# Patch.net
KiCad netlist of a schematic drawn in EAGLE
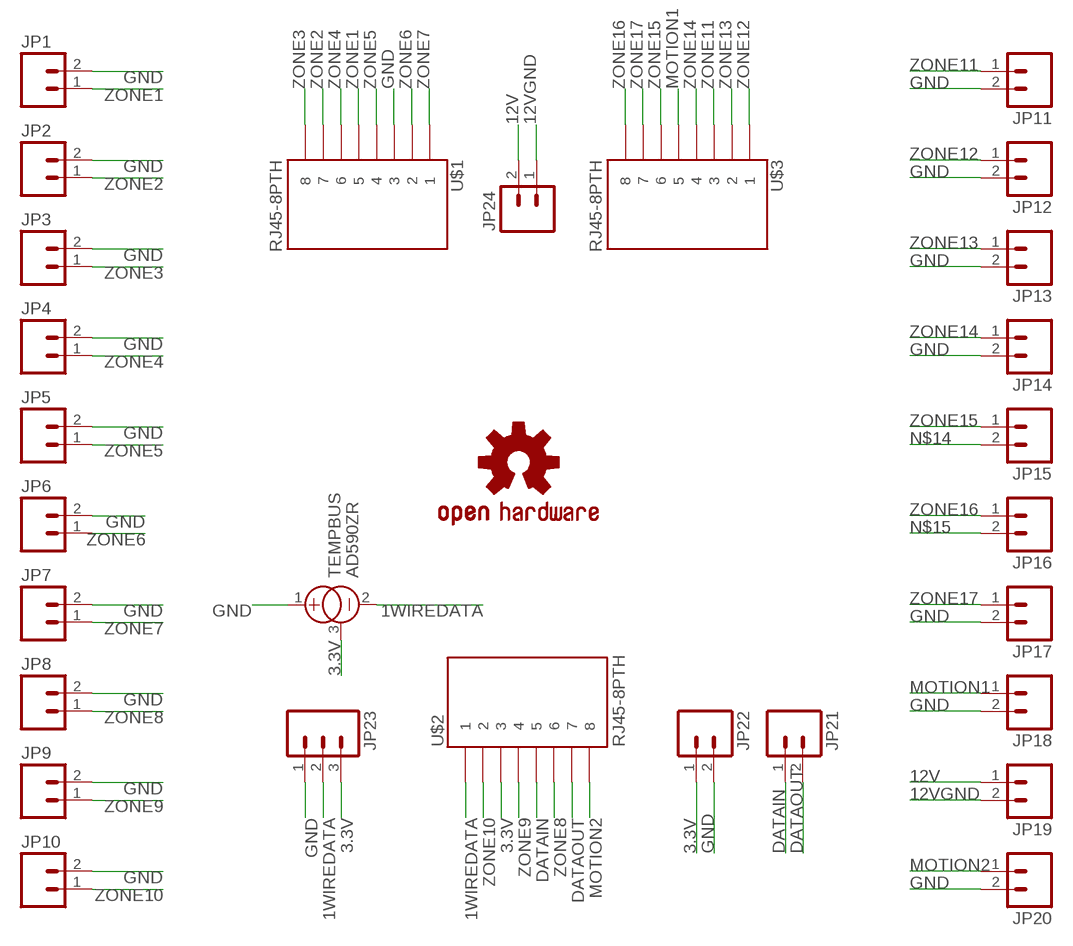
[diagram p0: schematic, sheet 1]

(export (version "E")
  (design (tool "Eeschema 10.0.6"))
  (components
    (comp (ref "JP1")
      (value "M023.5MM")
      (footprint "eagle-import:SCREWTERMINAL-3.5MM-2")
      (libsource (lib "eagle-import") (part "M023.5MM"))
    )
    (comp (ref "JP2")
      (value "M023.5MM")
      (footprint "eagle-import:SCREWTERMINAL-3.5MM-2")
      (libsource (lib "eagle-import") (part "M023.5MM"))
    )
    (comp (ref "JP3")
      (value "M023.5MM")
      (footprint "eagle-import:SCREWTERMINAL-3.5MM-2")
      (libsource (lib "eagle-import") (part "M023.5MM"))
    )
    (comp (ref "JP4")
      (value "M023.5MM")
      (footprint "eagle-import:SCREWTERMINAL-3.5MM-2")
      (libsource (lib "eagle-import") (part "M023.5MM"))
    )
    (comp (ref "JP5")
      (value "M023.5MM")
      (footprint "eagle-import:SCREWTERMINAL-3.5MM-2")
      (libsource (lib "eagle-import") (part "M023.5MM"))
    )
    (comp (ref "JP6")
      (value "M023.5MM")
      (footprint "eagle-import:SCREWTERMINAL-3.5MM-2")
      (libsource (lib "eagle-import") (part "M023.5MM"))
    )
    (comp (ref "JP7")
      (value "M023.5MM")
      (footprint "eagle-import:SCREWTERMINAL-3.5MM-2")
      (libsource (lib "eagle-import") (part "M023.5MM"))
    )
    (comp (ref "JP8")
      (value "M023.5MM")
      (footprint "eagle-import:SCREWTERMINAL-3.5MM-2")
      (libsource (lib "eagle-import") (part "M023.5MM"))
    )
    (comp (ref "JP9")
      (value "M023.5MM")
      (footprint "eagle-import:SCREWTERMINAL-3.5MM-2")
      (libsource (lib "eagle-import") (part "M023.5MM"))
    )
    (comp (ref "JP10")
      (value "M023.5MM")
      (footprint "eagle-import:SCREWTERMINAL-3.5MM-2")
      (libsource (lib "eagle-import") (part "M023.5MM"))
    )
    (comp (ref "JP11")
      (value "M023.5MM")
      (footprint "eagle-import:SCREWTERMINAL-3.5MM-2")
      (libsource (lib "eagle-import") (part "M023.5MM"))
    )
    (comp (ref "JP12")
      (value "M023.5MM")
      (footprint "eagle-import:SCREWTERMINAL-3.5MM-2")
      (libsource (lib "eagle-import") (part "M023.5MM"))
    )
    (comp (ref "JP13")
      (value "M023.5MM")
      (footprint "eagle-import:SCREWTERMINAL-3.5MM-2")
      (libsource (lib "eagle-import") (part "M023.5MM"))
    )
    (comp (ref "JP14")
      (value "M023.5MM")
      (footprint "eagle-import:SCREWTERMINAL-3.5MM-2")
      (libsource (lib "eagle-import") (part "M023.5MM"))
    )
    (comp (ref "JP15")
      (value "M023.5MM")
      (footprint "eagle-import:SCREWTERMINAL-3.5MM-2")
      (libsource (lib "eagle-import") (part "M023.5MM"))
    )
    (comp (ref "JP16")
      (value "M023.5MM")
      (footprint "eagle-import:SCREWTERMINAL-3.5MM-2")
      (libsource (lib "eagle-import") (part "M023.5MM"))
    )
    (comp (ref "JP17")
      (value "M023.5MM")
      (footprint "eagle-import:SCREWTERMINAL-3.5MM-2")
      (libsource (lib "eagle-import") (part "M023.5MM"))
    )
    (comp (ref "JP18")
      (value "M023.5MM")
      (footprint "eagle-import:SCREWTERMINAL-3.5MM-2")
      (libsource (lib "eagle-import") (part "M023.5MM"))
    )
    (comp (ref "JP19")
      (value "M023.5MM")
      (footprint "eagle-import:SCREWTERMINAL-3.5MM-2")
      (libsource (lib "eagle-import") (part "M023.5MM"))
    )
    (comp (ref "JP20")
      (value "M023.5MM")
      (footprint "eagle-import:SCREWTERMINAL-3.5MM-2")
      (libsource (lib "eagle-import") (part "M023.5MM"))
    )
    (comp (ref "JP21")
      (value "M023.5MM")
      (footprint "eagle-import:SCREWTERMINAL-3.5MM-2")
      (libsource (lib "eagle-import") (part "M023.5MM"))
    )
    (comp (ref "JP22")
      (value "M023.5MM")
      (footprint "eagle-import:SCREWTERMINAL-3.5MM-2")
      (libsource (lib "eagle-import") (part "M023.5MM"))
    )
    (comp (ref "JP23")
      (value "M03SCREW")
      (footprint "eagle-import:SCREWTERMINAL-3.5MM-3")
      (libsource (lib "eagle-import") (part "M03SCREW"))
    )
    (comp (ref "JP24")
      (value "M025MM")
      (footprint "eagle-import:SCREWTERMINAL-5MM-2")
      (libsource (lib "eagle-import") (part "M025MM"))
    )
    (comp (ref "TEMPBUS")
      (value "AD590ZR")
      (footprint "eagle-import:TO92")
      (libsource (lib "eagle-import") (part "AD590ZR"))
    )
    (comp (ref "U$1")
      (value "RJ45-8PTH")
      (footprint "eagle-import:RJ45-8")
      (libsource (lib "eagle-import") (part "RJ45-8PTH"))
    )
    (comp (ref "U$2")
      (value "RJ45-8PTH")
      (footprint "eagle-import:RJ45-8")
      (libsource (lib "eagle-import") (part "RJ45-8PTH"))
    )
    (comp (ref "U$3")
      (value "RJ45-8PTH")
      (footprint "eagle-import:RJ45-8")
      (libsource (lib "eagle-import") (part "RJ45-8PTH"))
    )
    (comp (ref "U$4")
      (value "OSHW-LOGOL")
      (footprint "eagle-import:OSHW-LOGO-L")
      (libsource (lib "eagle-import") (part "OSHW-LOGOL"))
    )
  )
  (nets
    (net (code "1") (name "/1WIREDATA") (class "Default")
      (node (ref "JP23") (pin "2") (pinfunction "2_2") (pintype "passive"))
      (node (ref "TEMPBUS") (pin "2") (pinfunction "-_2") (pintype "input"))
      (node (ref "U$2") (pin "1") (pinfunction "1_1") (pintype "bidirectional"))
    )
    (net (code "2") (name "/3.3V") (class "Default")
      (node (ref "JP22") (pin "1") (pinfunction "1_1") (pintype "passive"))
      (node (ref "JP23") (pin "3") (pinfunction "3_3") (pintype "passive"))
      (node (ref "TEMPBUS") (pin "3") (pinfunction "CAN_3") (pintype "passive"))
      (node (ref "U$2") (pin "3") (pinfunction "3_3") (pintype "bidirectional"))
    )
    (net (code "3") (name "/12V") (class "Default")
      (node (ref "JP19") (pin "1") (pinfunction "1_1") (pintype "passive"))
      (node (ref "JP24") (pin "2") (pinfunction "2_2") (pintype "passive"))
    )
    (net (code "4") (name "/12VGND") (class "Default")
      (node (ref "JP19") (pin "2") (pinfunction "2_2") (pintype "passive"))
      (node (ref "JP24") (pin "1") (pinfunction "1_1") (pintype "passive"))
    )
    (net (code "5") (name "/DATAIN") (class "Default")
      (node (ref "JP21") (pin "1") (pinfunction "1_1") (pintype "passive"))
      (node (ref "U$2") (pin "5") (pinfunction "5_5") (pintype "bidirectional"))
    )
    (net (code "6") (name "/DATAOUT") (class "Default")
      (node (ref "JP21") (pin "2") (pinfunction "2_2") (pintype "passive"))
      (node (ref "U$2") (pin "7") (pinfunction "7_7") (pintype "bidirectional"))
    )
    (net (code "7") (name "/GND") (class "Default")
      (node (ref "JP1") (pin "2") (pinfunction "2_2") (pintype "passive"))
      (node (ref "JP10") (pin "2") (pinfunction "2_2") (pintype "passive"))
      (node (ref "JP11") (pin "2") (pinfunction "2_2") (pintype "passive"))
      (node (ref "JP12") (pin "2") (pinfunction "2_2") (pintype "passive"))
      (node (ref "JP13") (pin "2") (pinfunction "2_2") (pintype "passive"))
      (node (ref "JP14") (pin "2") (pinfunction "2_2") (pintype "passive"))
      (node (ref "JP17") (pin "2") (pinfunction "2_2") (pintype "passive"))
      (node (ref "JP18") (pin "2") (pinfunction "2_2") (pintype "passive"))
      (node (ref "JP2") (pin "2") (pinfunction "2_2") (pintype "passive"))
      (node (ref "JP20") (pin "2") (pinfunction "2_2") (pintype "passive"))
      (node (ref "JP22") (pin "2") (pinfunction "2_2") (pintype "passive"))
      (node (ref "JP23") (pin "1") (pinfunction "1_1") (pintype "passive"))
      (node (ref "JP3") (pin "2") (pinfunction "2_2") (pintype "passive"))
      (node (ref "JP4") (pin "2") (pinfunction "2_2") (pintype "passive"))
      (node (ref "JP5") (pin "2") (pinfunction "2_2") (pintype "passive"))
      (node (ref "JP6") (pin "2") (pinfunction "2_2") (pintype "passive"))
      (node (ref "JP7") (pin "2") (pinfunction "2_2") (pintype "passive"))
      (node (ref "JP8") (pin "2") (pinfunction "2_2") (pintype "passive"))
      (node (ref "JP9") (pin "2") (pinfunction "2_2") (pintype "passive"))
      (node (ref "TEMPBUS") (pin "1") (pinfunction "+_1") (pintype "input"))
      (node (ref "U$1") (pin "3") (pinfunction "3_3") (pintype "bidirectional"))
    )
    (net (code "8") (name "/MOTION1") (class "Default")
      (node (ref "JP18") (pin "1") (pinfunction "1_1") (pintype "passive"))
      (node (ref "U$3") (pin "5") (pinfunction "5_5") (pintype "bidirectional"))
    )
    (net (code "9") (name "/MOTION2") (class "Default")
      (node (ref "JP20") (pin "1") (pinfunction "1_1") (pintype "passive"))
      (node (ref "U$2") (pin "8") (pinfunction "8_8") (pintype "bidirectional"))
    )
    (net (code "10") (name "/N$14") (class "Default")
      (node (ref "JP15") (pin "2") (pinfunction "2_2") (pintype "passive"))
    )
    (net (code "11") (name "/N$15") (class "Default")
      (node (ref "JP16") (pin "2") (pinfunction "2_2") (pintype "passive"))
    )
    (net (code "12") (name "/ZONE1") (class "Default")
      (node (ref "JP1") (pin "1") (pinfunction "1_1") (pintype "passive"))
      (node (ref "U$1") (pin "5") (pinfunction "5_5") (pintype "bidirectional"))
    )
    (net (code "13") (name "/ZONE2") (class "Default")
      (node (ref "JP2") (pin "1") (pinfunction "1_1") (pintype "passive"))
      (node (ref "U$1") (pin "7") (pinfunction "7_7") (pintype "bidirectional"))
    )
    (net (code "14") (name "/ZONE3") (class "Default")
      (node (ref "JP3") (pin "1") (pinfunction "1_1") (pintype "passive"))
      (node (ref "U$1") (pin "8") (pinfunction "8_8") (pintype "bidirectional"))
    )
    (net (code "15") (name "/ZONE4") (class "Default")
      (node (ref "JP4") (pin "1") (pinfunction "1_1") (pintype "passive"))
      (node (ref "U$1") (pin "6") (pinfunction "6_6") (pintype "bidirectional"))
    )
    (net (code "16") (name "/ZONE5") (class "Default")
      (node (ref "JP5") (pin "1") (pinfunction "1_1") (pintype "passive"))
      (node (ref "U$1") (pin "4") (pinfunction "4_4") (pintype "bidirectional"))
    )
    (net (code "17") (name "/ZONE6") (class "Default")
      (node (ref "JP6") (pin "1") (pinfunction "1_1") (pintype "passive"))
      (node (ref "U$1") (pin "2") (pinfunction "2_2") (pintype "bidirectional"))
    )
    (net (code "18") (name "/ZONE7") (class "Default")
      (node (ref "JP7") (pin "1") (pinfunction "1_1") (pintype "passive"))
      (node (ref "U$1") (pin "1") (pinfunction "1_1") (pintype "bidirectional"))
    )
    (net (code "19") (name "/ZONE8") (class "Default")
      (node (ref "JP8") (pin "1") (pinfunction "1_1") (pintype "passive"))
      (node (ref "U$2") (pin "6") (pinfunction "6_6") (pintype "bidirectional"))
    )
    (net (code "20") (name "/ZONE9") (class "Default")
      (node (ref "JP9") (pin "1") (pinfunction "1_1") (pintype "passive"))
      (node (ref "U$2") (pin "4") (pinfunction "4_4") (pintype "bidirectional"))
    )
    (net (code "21") (name "/ZONE10") (class "Default")
      (node (ref "JP10") (pin "1") (pinfunction "1_1") (pintype "passive"))
      (node (ref "U$2") (pin "2") (pinfunction "2_2") (pintype "bidirectional"))
    )
    (net (code "22") (name "/ZONE11") (class "Default")
      (node (ref "JP11") (pin "1") (pinfunction "1_1") (pintype "passive"))
      (node (ref "U$3") (pin "3") (pinfunction "3_3") (pintype "bidirectional"))
    )
    (net (code "23") (name "/ZONE12") (class "Default")
      (node (ref "JP12") (pin "1") (pinfunction "1_1") (pintype "passive"))
      (node (ref "U$3") (pin "1") (pinfunction "1_1") (pintype "bidirectional"))
    )
    (net (code "24") (name "/ZONE13") (class "Default")
      (node (ref "JP13") (pin "1") (pinfunction "1_1") (pintype "passive"))
      (node (ref "U$3") (pin "2") (pinfunction "2_2") (pintype "bidirectional"))
    )
    (net (code "25") (name "/ZONE14") (class "Default")
      (node (ref "JP14") (pin "1") (pinfunction "1_1") (pintype "passive"))
      (node (ref "U$3") (pin "4") (pinfunction "4_4") (pintype "bidirectional"))
    )
    (net (code "26") (name "/ZONE15") (class "Default")
      (node (ref "JP15") (pin "1") (pinfunction "1_1") (pintype "passive"))
      (node (ref "U$3") (pin "6") (pinfunction "6_6") (pintype "bidirectional"))
    )
    (net (code "27") (name "/ZONE16") (class "Default")
      (node (ref "JP16") (pin "1") (pinfunction "1_1") (pintype "passive"))
      (node (ref "U$3") (pin "8") (pinfunction "8_8") (pintype "bidirectional"))
    )
    (net (code "28") (name "/ZONE17") (class "Default")
      (node (ref "JP17") (pin "1") (pinfunction "1_1") (pintype "passive"))
      (node (ref "U$3") (pin "7") (pinfunction "7_7") (pintype "bidirectional"))
    )
  )
)
